# kickerv3.net
KiCad netlist of a schematic drawn in EAGLE
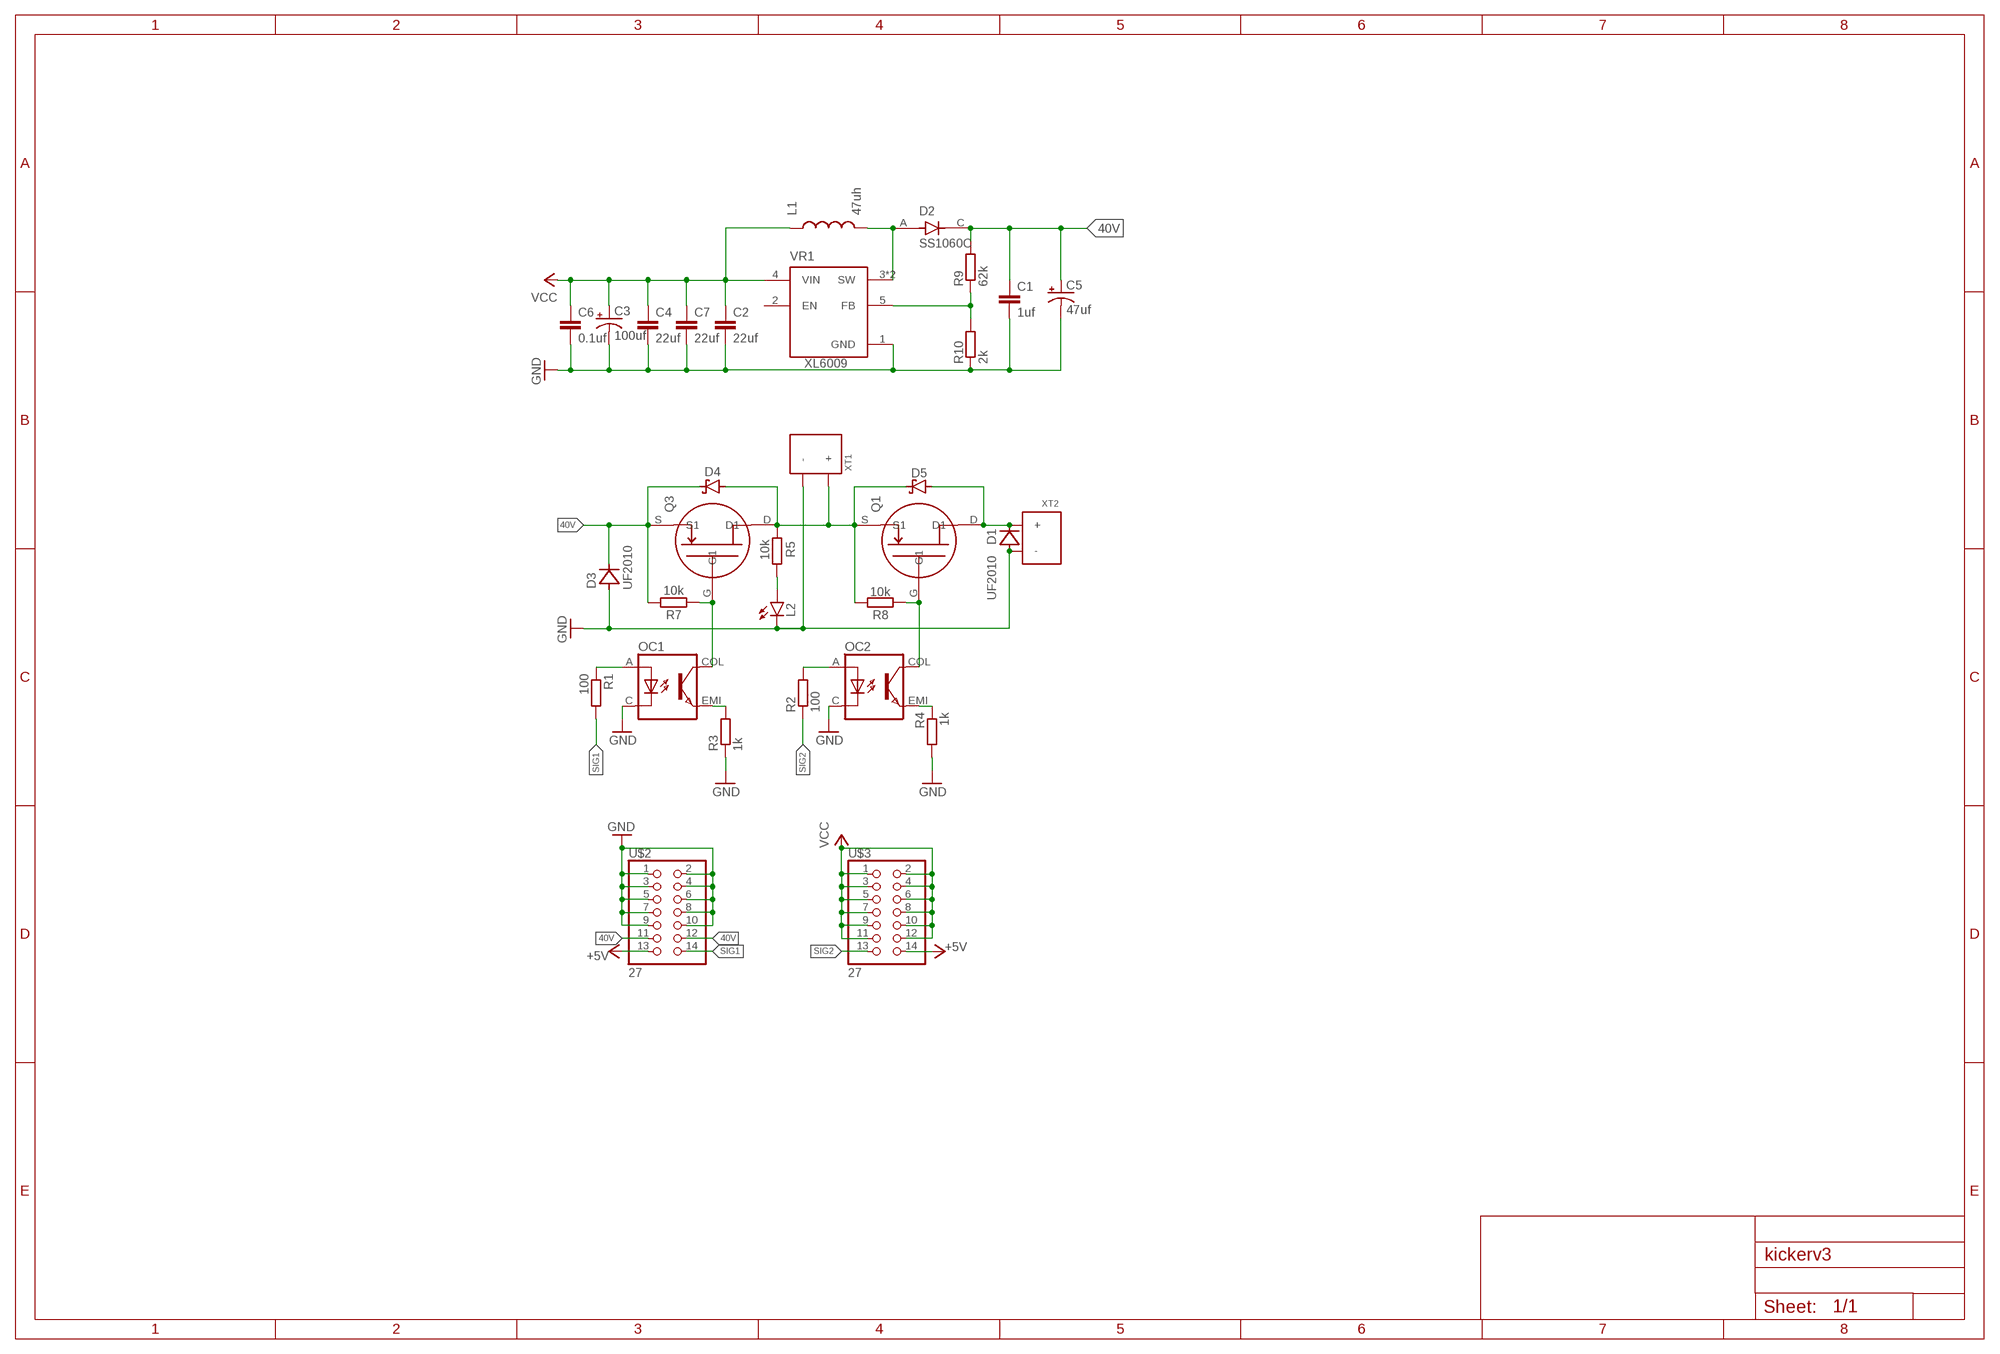
[diagram p0: schematic, sheet 1]

(export (version "E")
  (design (tool "Eeschema 10.0.6"))
  (components
    (comp (ref "C1")
      (value "1uf")
      (footprint "eagle-import:C1206")
      (libsource (lib "eagle-import") (part "C-EUC1206"))
    )
    (comp (ref "C2")
      (value "22uf")
      (footprint "eagle-import:C0805")
      (libsource (lib "eagle-import") (part "C-EUC0805"))
    )
    (comp (ref "C3")
      (value "100uf")
      (footprint "eagle-import:MH5")
      (libsource (lib "eagle-import") (part "MH5"))
    )
    (comp (ref "C4")
      (value "22uf")
      (footprint "eagle-import:C0805")
      (libsource (lib "eagle-import") (part "C-EUC0805"))
    )
    (comp (ref "C5")
      (value "47uf")
      (footprint "eagle-import:VZ1H470ME077000CE0")
      (libsource (lib "eagle-import") (part "VZ1H470ME077000CE0"))
    )
    (comp (ref "C6")
      (value "0.1uf")
      (footprint "eagle-import:C0603")
      (libsource (lib "eagle-import") (part "C-EUC0603"))
    )
    (comp (ref "C7")
      (value "22uf")
      (footprint "eagle-import:C0805")
      (libsource (lib "eagle-import") (part "C-EUC0805"))
    )
    (comp (ref "D1")
      (value "UF2010")
      (footprint "eagle-import:UF2010")
      (libsource (lib "eagle-import") (part "UF2010"))
    )
    (comp (ref "D2")
      (value "SS1060C")
      (footprint "eagle-import:DIOSC6959X240")
      (fields (field (name "MF") "Diotec Semiconductor") (field (name "MP") "SK36"))
      (libsource (lib "eagle-import") (part "SS1060C"))
    )
    (comp (ref "D3")
      (value "UF2010")
      (footprint "eagle-import:UF2010")
      (libsource (lib "eagle-import") (part "UF2010"))
    )
    (comp (ref "D4")
      (value "1SS178")
      (footprint "eagle-import:1SS178")
      (libsource (lib "eagle-import") (part "1SS178"))
    )
    (comp (ref "D5")
      (value "1SS178")
      (footprint "eagle-import:1SS178")
      (libsource (lib "eagle-import") (part "1SS178"))
    )
    (comp (ref "L1")
      (value "47uh")
      (footprint "eagle-import:MDE1040-470M")
      (libsource (lib "eagle-import") (part "MDE1040-470M"))
    )
    (comp (ref "L2")
      (value "SML-E12P8WT86")
      (footprint "eagle-import:LED_SML-LXFM0603SIC-TR")
      (libsource (lib "eagle-import") (part "SML-E12P8WT86"))
    )
    (comp (ref "OC1")
      (value "TL293(GB)")
      (footprint "eagle-import:SOIC127P700X230-4N")
      (libsource (lib "eagle-import") (part "TL293(GB)"))
    )
    (comp (ref "OC2")
      (value "TL293(GB)")
      (footprint "eagle-import:SOIC127P700X230-4N")
      (libsource (lib "eagle-import") (part "TL293(GB)"))
    )
    (comp (ref "Q1")
      (value "TJ60S04M3L")
      (footprint "eagle-import:DPACK")
      (libsource (lib "eagle-import") (part "TJ60S04M3L"))
    )
    (comp (ref "Q3")
      (value "TJ60S04M3L")
      (footprint "eagle-import:DPACK")
      (libsource (lib "eagle-import") (part "TJ60S04M3L"))
    )
    (comp (ref "R1")
      (value "100")
      (footprint "eagle-import:R0603")
      (libsource (lib "eagle-import") (part "R-EU_R0603"))
    )
    (comp (ref "R2")
      (value "100")
      (footprint "eagle-import:R0603")
      (libsource (lib "eagle-import") (part "R-EU_R0603"))
    )
    (comp (ref "R3")
      (value "1k")
      (footprint "eagle-import:R0603")
      (libsource (lib "eagle-import") (part "R-EU_R0603"))
    )
    (comp (ref "R4")
      (value "1k")
      (footprint "eagle-import:R0603")
      (libsource (lib "eagle-import") (part "R-EU_R0603"))
    )
    (comp (ref "R5")
      (value "10k")
      (footprint "eagle-import:R0603")
      (libsource (lib "eagle-import") (part "R-EU_R0603"))
    )
    (comp (ref "R7")
      (value "10k")
      (footprint "eagle-import:R0603")
      (libsource (lib "eagle-import") (part "R-EU_R0603"))
    )
    (comp (ref "R8")
      (value "10k")
      (footprint "eagle-import:R0603")
      (libsource (lib "eagle-import") (part "R-EU_R0603"))
    )
    (comp (ref "R9")
      (value "62k")
      (footprint "eagle-import:R0603")
      (libsource (lib "eagle-import") (part "R-EU_R0603"))
    )
    (comp (ref "R10")
      (value "2k")
      (footprint "eagle-import:R0603")
      (libsource (lib "eagle-import") (part "R-EU_R0603"))
    )
    (comp (ref "U$2")
      (value "27")
      (footprint "eagle-import:2_7")
      (libsource (lib "eagle-import") (part "27"))
    )
    (comp (ref "U$3")
      (value "27")
      (footprint "eagle-import:2_7")
      (libsource (lib "eagle-import") (part "27"))
    )
    (comp (ref "VR1")
      (value "XL6009")
      (footprint "eagle-import:DPAK170P1435X465-6N")
      (fields (field (name "MF") "XLSEMI"))
      (libsource (lib "eagle-import") (part "XL6009"))
    )
    (comp (ref "XT1")
      (value "XT30PW-F")
      (footprint "eagle-import:XT30PW-F")
      (libsource (lib "eagle-import") (part "XT30PW-F"))
    )
    (comp (ref "XT2")
      (value "XT30PW-F")
      (footprint "eagle-import:XT30PW-F")
      (libsource (lib "eagle-import") (part "XT30PW-F"))
    )
  )
  (nets
    (net (code "1") (name "+5V") (class "Default")
      (node (ref "U$2") (pin "13") (pinfunction "13_13") (pintype "passive"))
      (node (ref "U$3") (pin "14") (pinfunction "14_14") (pintype "passive"))
    )
    (net (code "2") (name "40V") (class "Default")
      (node (ref "C1") (pin "1") (pinfunction "1_1") (pintype "passive"))
      (node (ref "C5") (pin "+") (pinfunction "+_+") (pintype "passive"))
      (node (ref "D2") (pin "C") (pinfunction "C_C") (pintype "passive"))
      (node (ref "D3") (pin "C") (pinfunction "C_C") (pintype "passive"))
      (node (ref "D4") (pin "C") (pinfunction "C_C") (pintype "passive"))
      (node (ref "Q3") (pin "S") (pinfunction "S1_S") (pintype "bidirectional"))
      (node (ref "R7") (pin "1") (pinfunction "1_1") (pintype "passive"))
      (node (ref "R9") (pin "2") (pinfunction "2_2") (pintype "passive"))
      (node (ref "U$2") (pin "11") (pinfunction "11_11") (pintype "passive"))
      (node (ref "U$2") (pin "12") (pinfunction "12_12") (pintype "passive"))
    )
    (net (code "3") (name "GND") (class "Default")
      (node (ref "C1") (pin "2") (pinfunction "2_2") (pintype "passive"))
      (node (ref "C2") (pin "2") (pinfunction "2_2") (pintype "passive"))
      (node (ref "C3") (pin "-") (pinfunction "-_-") (pintype "passive"))
      (node (ref "C4") (pin "2") (pinfunction "2_2") (pintype "passive"))
      (node (ref "C5") (pin "-") (pinfunction "-_-") (pintype "passive"))
      (node (ref "C6") (pin "2") (pinfunction "2_2") (pintype "passive"))
      (node (ref "C7") (pin "2") (pinfunction "2_2") (pintype "passive"))
      (node (ref "D1") (pin "A") (pinfunction "A_A") (pintype "passive"))
      (node (ref "D3") (pin "A") (pinfunction "A_A") (pintype "passive"))
      (node (ref "L2") (pin "C") (pinfunction "C_C") (pintype "passive"))
      (node (ref "OC1") (pin "C") (pinfunction "C_C") (pintype "passive"))
      (node (ref "OC2") (pin "C") (pinfunction "C_C") (pintype "passive"))
      (node (ref "R10") (pin "1") (pinfunction "1_1") (pintype "passive"))
      (node (ref "R3") (pin "1") (pinfunction "1_1") (pintype "passive"))
      (node (ref "R4") (pin "2") (pinfunction "2_2") (pintype "passive"))
      (node (ref "U$2") (pin "1") (pinfunction "1_1") (pintype "passive"))
      (node (ref "U$2") (pin "10") (pinfunction "10_10") (pintype "passive"))
      (node (ref "U$2") (pin "2") (pinfunction "2_2") (pintype "passive"))
      (node (ref "U$2") (pin "3") (pinfunction "3_3") (pintype "passive"))
      (node (ref "U$2") (pin "4") (pinfunction "4_4") (pintype "passive"))
      (node (ref "U$2") (pin "5") (pinfunction "5_5") (pintype "passive"))
      (node (ref "U$2") (pin "6") (pinfunction "6_6") (pintype "passive"))
      (node (ref "U$2") (pin "7") (pinfunction "7_7") (pintype "passive"))
      (node (ref "U$2") (pin "8") (pinfunction "8_8") (pintype "passive"))
      (node (ref "U$2") (pin "9") (pinfunction "9_9") (pintype "passive"))
      (node (ref "VR1") (pin "1") (pinfunction "GND_1") (pintype "power_in"))
      (node (ref "XT1") (pin "-") (pinfunction "-_-") (pintype "bidirectional"))
      (node (ref "XT2") (pin "-") (pinfunction "-_-") (pintype "bidirectional"))
    )
    (net (code "4") (name "Net-(L1-2)") (class "Default")
      (node (ref "D2") (pin "A") (pinfunction "A_A") (pintype "passive"))
      (node (ref "L1") (pin "P$2") (pinfunction "2_P$2") (pintype "passive"))
      (node (ref "VR1") (pin "3") (pinfunction "SW_3") (pintype "output"))
      (node (ref "VR1") (pin "6") (pinfunction "SW_6") (pintype "output"))
    )
    (net (code "5") (name "Net-(L2-PadA)") (class "Default")
      (node (ref "L2") (pin "A") (pinfunction "A_A") (pintype "passive"))
      (node (ref "R5") (pin "1") (pinfunction "1_1") (pintype "passive"))
    )
    (net (code "6") (name "Net-(OC1-PadA)") (class "Default")
      (node (ref "OC1") (pin "A") (pinfunction "A_A") (pintype "passive"))
      (node (ref "R1") (pin "1") (pinfunction "1_1") (pintype "passive"))
    )
    (net (code "7") (name "Net-(OC1-PadEMI)") (class "Default")
      (node (ref "OC1") (pin "EMI") (pinfunction "EMI_EMI") (pintype "passive"))
      (node (ref "R3") (pin "2") (pinfunction "2_2") (pintype "passive"))
    )
    (net (code "8") (name "Net-(OC2-PadA)") (class "Default")
      (node (ref "OC2") (pin "A") (pinfunction "A_A") (pintype "passive"))
      (node (ref "R2") (pin "2") (pinfunction "2_2") (pintype "passive"))
    )
    (net (code "9") (name "Net-(OC2-PadEMI)") (class "Default")
      (node (ref "OC2") (pin "EMI") (pinfunction "EMI_EMI") (pintype "passive"))
      (node (ref "R4") (pin "1") (pinfunction "1_1") (pintype "passive"))
    )
    (net (code "10") (name "Net-(Q1-D1)") (class "Default")
      (node (ref "D1") (pin "C") (pinfunction "C_C") (pintype "passive"))
      (node (ref "D5") (pin "A") (pinfunction "A_A") (pintype "passive"))
      (node (ref "Q1") (pin "D") (pinfunction "D1_D") (pintype "bidirectional"))
      (node (ref "XT2") (pin "+") (pinfunction "+_+") (pintype "bidirectional"))
    )
    (net (code "11") (name "Net-(Q1-G1)") (class "Default")
      (node (ref "OC2") (pin "COL") (pinfunction "COL_COL") (pintype "passive"))
      (node (ref "Q1") (pin "G") (pinfunction "G1_G") (pintype "bidirectional"))
      (node (ref "R8") (pin "2") (pinfunction "2_2") (pintype "passive"))
    )
    (net (code "12") (name "Net-(Q1-S1)") (class "Default")
      (node (ref "D4") (pin "A") (pinfunction "A_A") (pintype "passive"))
      (node (ref "D5") (pin "C") (pinfunction "C_C") (pintype "passive"))
      (node (ref "Q1") (pin "S") (pinfunction "S1_S") (pintype "bidirectional"))
      (node (ref "Q3") (pin "D") (pinfunction "D1_D") (pintype "bidirectional"))
      (node (ref "R5") (pin "2") (pinfunction "2_2") (pintype "passive"))
      (node (ref "R8") (pin "1") (pinfunction "1_1") (pintype "passive"))
      (node (ref "XT1") (pin "+") (pinfunction "+_+") (pintype "bidirectional"))
    )
    (net (code "13") (name "Net-(Q3-G1)") (class "Default")
      (node (ref "OC1") (pin "COL") (pinfunction "COL_COL") (pintype "passive"))
      (node (ref "Q3") (pin "G") (pinfunction "G1_G") (pintype "bidirectional"))
      (node (ref "R7") (pin "2") (pinfunction "2_2") (pintype "passive"))
    )
    (net (code "14") (name "Net-(VR1-FB)") (class "Default")
      (node (ref "R10") (pin "2") (pinfunction "2_2") (pintype "passive"))
      (node (ref "R9") (pin "1") (pinfunction "1_1") (pintype "passive"))
      (node (ref "VR1") (pin "5") (pinfunction "FB_5") (pintype "input"))
    )
    (net (code "15") (name "SIG1") (class "Default")
      (node (ref "R1") (pin "2") (pinfunction "2_2") (pintype "passive"))
      (node (ref "U$2") (pin "14") (pinfunction "14_14") (pintype "passive"))
    )
    (net (code "16") (name "SIG2") (class "Default")
      (node (ref "R2") (pin "1") (pinfunction "1_1") (pintype "passive"))
      (node (ref "U$3") (pin "13") (pinfunction "13_13") (pintype "passive"))
    )
    (net (code "17") (name "VCC") (class "Default")
      (node (ref "C2") (pin "1") (pinfunction "1_1") (pintype "passive"))
      (node (ref "C3") (pin "+") (pinfunction "+_+") (pintype "passive"))
      (node (ref "C4") (pin "1") (pinfunction "1_1") (pintype "passive"))
      (node (ref "C6") (pin "1") (pinfunction "1_1") (pintype "passive"))
      (node (ref "C7") (pin "1") (pinfunction "1_1") (pintype "passive"))
      (node (ref "L1") (pin "P$1") (pinfunction "1_P$1") (pintype "passive"))
      (node (ref "U$3") (pin "1") (pinfunction "1_1") (pintype "passive"))
      (node (ref "U$3") (pin "10") (pinfunction "10_10") (pintype "passive"))
      (node (ref "U$3") (pin "11") (pinfunction "11_11") (pintype "passive"))
      (node (ref "U$3") (pin "12") (pinfunction "12_12") (pintype "passive"))
      (node (ref "U$3") (pin "2") (pinfunction "2_2") (pintype "passive"))
      (node (ref "U$3") (pin "3") (pinfunction "3_3") (pintype "passive"))
      (node (ref "U$3") (pin "4") (pinfunction "4_4") (pintype "passive"))
      (node (ref "U$3") (pin "5") (pinfunction "5_5") (pintype "passive"))
      (node (ref "U$3") (pin "6") (pinfunction "6_6") (pintype "passive"))
      (node (ref "U$3") (pin "7") (pinfunction "7_7") (pintype "passive"))
      (node (ref "U$3") (pin "8") (pinfunction "8_8") (pintype "passive"))
      (node (ref "U$3") (pin "9") (pinfunction "9_9") (pintype "passive"))
      (node (ref "VR1") (pin "4") (pinfunction "VIN_4") (pintype "input"))
    )
    (net (code "18") (name "unconnected-(VR1-EN-Pad2)") (class "Default")
      (node (ref "VR1") (pin "2") (pinfunction "EN_2") (pintype "input"))
    )
  )
)
